# Sediment_Board.net
KiCad netlist of a schematic drawn in EAGLE
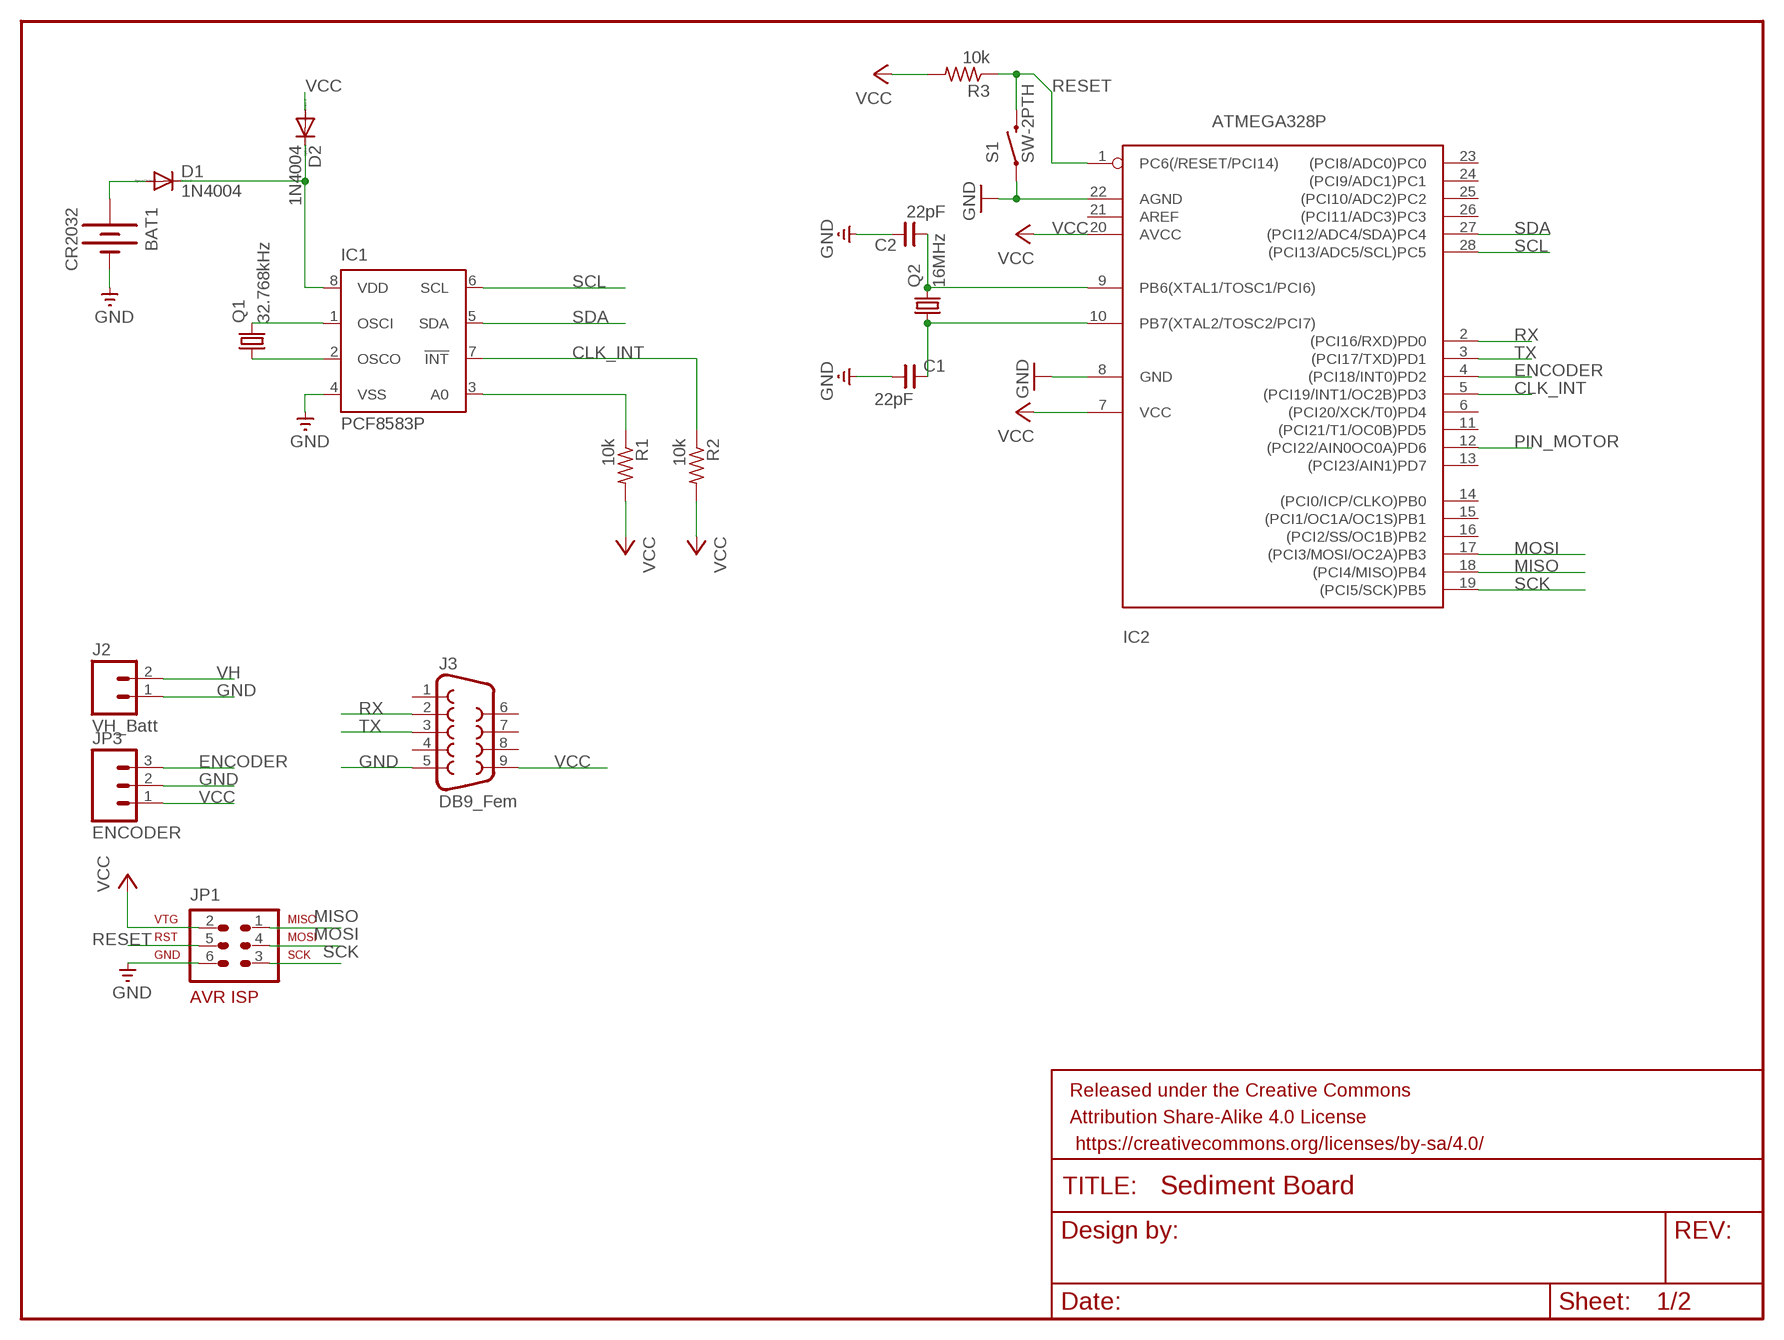
[diagram p0: schematic, sheet 1]
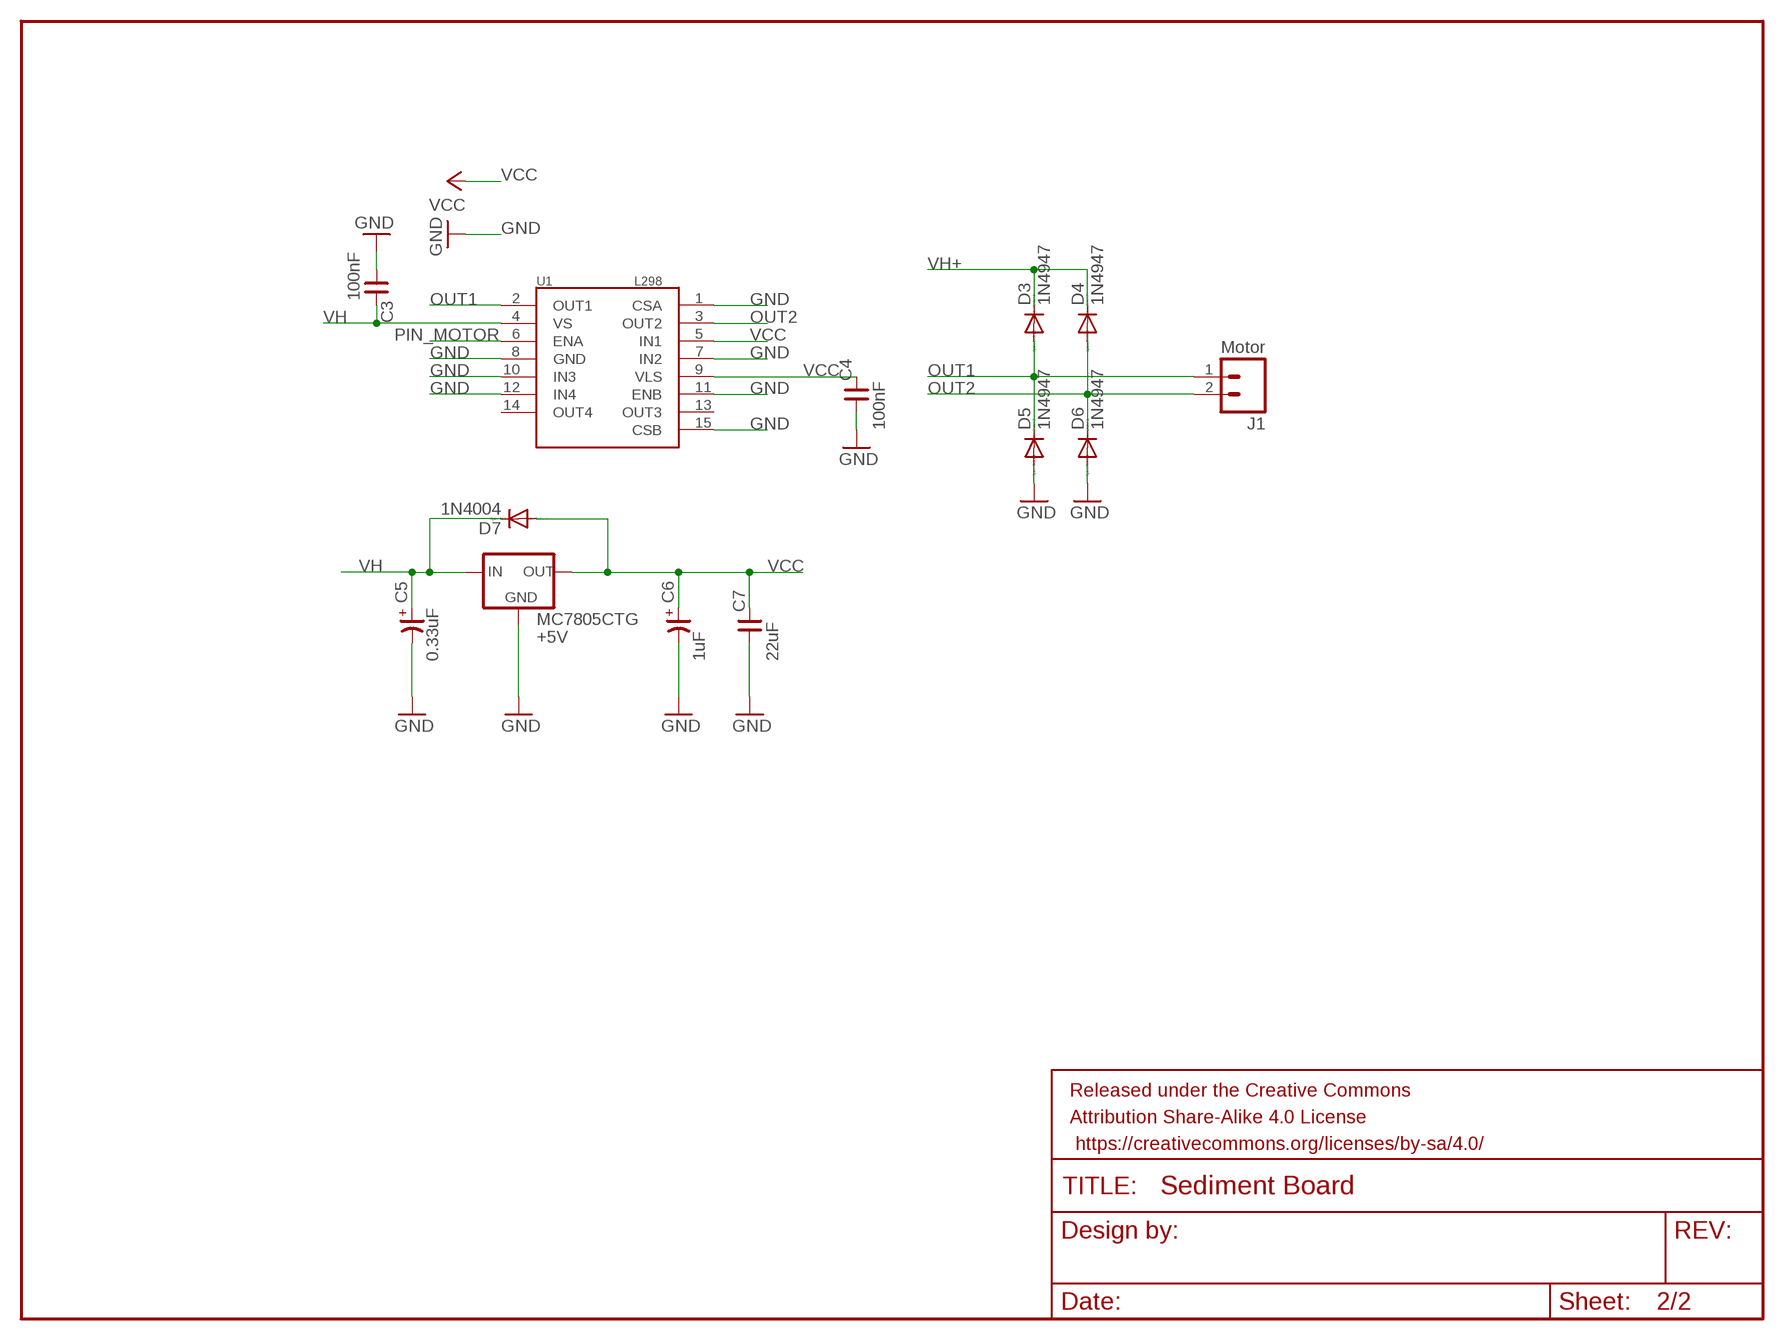
[diagram p1: schematic, sheet 2]

(export (version "E")
  (design (tool "Eeschema 10.0.6"))
  (components
    (comp (ref "C3")
      (value "100nF")
      (footprint "eagle-import:C025-050X025")
      (libsource (lib "eagle-import") (part "CNP-C025-050X025"))
    )
    (comp (ref "C4")
      (value "100nF")
      (footprint "eagle-import:C025-050X025")
      (libsource (lib "eagle-import") (part "CNP-C025-050X025"))
    )
    (comp (ref "C5")
      (value "0.33uF")
      (footprint "eagle-import:TT-025-040")
      (libsource (lib "eagle-import") (part "CP-TT025-040"))
    )
    (comp (ref "C6")
      (value "1uF")
      (footprint "eagle-import:TT-025-040")
      (libsource (lib "eagle-import") (part "CP-TT025-040"))
    )
    (comp (ref "C7")
      (value "22uF")
      (footprint "eagle-import:C025-050X025")
      (libsource (lib "eagle-import") (part "CNP-C025-050X025"))
    )
    (comp (ref "D3")
      (value "1N4947")
      (footprint "eagle-import:DO41-10")
      (libsource (lib "eagle-import") (part "1N4942"))
    )
    (comp (ref "D4")
      (value "1N4947")
      (footprint "eagle-import:DO41-10")
      (libsource (lib "eagle-import") (part "1N4942"))
    )
    (comp (ref "D5")
      (value "1N4947")
      (footprint "eagle-import:DO41-10")
      (libsource (lib "eagle-import") (part "1N4942"))
    )
    (comp (ref "D6")
      (value "1N4947")
      (footprint "eagle-import:DO41-10")
      (libsource (lib "eagle-import") (part "1N4942"))
    )
    (comp (ref "D7")
      (value "1N4004")
      (footprint "eagle-import:DO41-10")
      (libsource (lib "eagle-import") (part "1N4004"))
    )
    (comp (ref "FRAME2")
      (value "FRAME-LETTER")
      (footprint "eagle-import:CREATIVE_COMMONS")
      (libsource (lib "eagle-import") (part "FRAME-LETTER"))
    )
    (comp (ref "J1")
      (value "Motor")
      (footprint "eagle-import:SCREWTERMINAL-3.5MM-2")
      (libsource (lib "eagle-import") (part "M023.5MM"))
    )
    (comp (ref "MC7805CTG")
      (value "+5V")
      (footprint "eagle-import:78XXL")
      (libsource (lib "eagle-import") (part "V_REG_78XXSIDE"))
    )
    (comp (ref "U1")
      (value "L298")
      (footprint "eagle-import:MULTIWATT15")
      (libsource (lib "eagle-import") (part "L298"))
    )
    (comp (ref "BAT1")
      (value "CR2032")
      (footprint "eagle-import:BATTCOM_20MM_PTH")
      (libsource (lib "eagle-import") (part "BATTERY20PTH"))
    )
    (comp (ref "C1")
      (value "22pF")
      (footprint "eagle-import:C025-050X025")
      (libsource (lib "eagle-import") (part "CNP-C025-050X025"))
    )
    (comp (ref "C2")
      (value "22pF")
      (footprint "eagle-import:C025-050X025")
      (libsource (lib "eagle-import") (part "CNP-C025-050X025"))
    )
    (comp (ref "D1")
      (value "1N4004")
      (footprint "eagle-import:DO41-10")
      (libsource (lib "eagle-import") (part "1N4004"))
    )
    (comp (ref "D2")
      (value "1N4004")
      (footprint "eagle-import:DO41-10")
      (libsource (lib "eagle-import") (part "1N4004"))
    )
    (comp (ref "FRAME1")
      (value "FRAME-LETTER")
      (footprint "eagle-import:CREATIVE_COMMONS")
      (libsource (lib "eagle-import") (part "FRAME-LETTER"))
    )
    (comp (ref "IC1")
      (value "PCF8583P")
      (footprint "eagle-import:DIL08")
      (libsource (lib "eagle-import") (part "PCF8583P"))
    )
    (comp (ref "IC2")
      (value "ATMEGA328P")
      (footprint "eagle-import:DIL28-3-ROUND")
      (libsource (lib "eagle-import") (part "ATMEGA328PROUND"))
    )
    (comp (ref "J2")
      (value "VH_Batt")
      (footprint "eagle-import:SCREWTERMINAL-3.5MM-2")
      (libsource (lib "eagle-import") (part "M023.5MM"))
    )
    (comp (ref "J3")
      (value "DB9_Fem")
      (footprint "eagle-import:DB9")
      (libsource (lib "eagle-import") (part "DB9FEMALE"))
    )
    (comp (ref "JP1")
      (value "AVR-ISP-6")
      (footprint "eagle-import:AVR-ISP-6")
      (libsource (lib "eagle-import") (part "AVR-ISP-6"))
    )
    (comp (ref "JP3")
      (value "ENCODER")
      (footprint "eagle-import:MOLEX-1X3")
      (libsource (lib "eagle-import") (part "M03POLAR"))
    )
    (comp (ref "Q1")
      (value "32.768kHz")
      (footprint "eagle-import:TC26H")
      (libsource (lib "eagle-import") (part "CRYSTALTC26H"))
    )
    (comp (ref "Q2")
      (value "16MHz")
      (footprint "eagle-import:HC49U70")
      (libsource (lib "eagle-import") (part "CRYSTALHC49U70"))
    )
    (comp (ref "R1")
      (value "10k")
      (footprint "eagle-import:0207_10")
      (libsource (lib "eagle-import") (part "R-US_0207/10"))
    )
    (comp (ref "R2")
      (value "10k")
      (footprint "eagle-import:0207_10")
      (libsource (lib "eagle-import") (part "R-US_0207/10"))
    )
    (comp (ref "R3")
      (value "10k")
      (footprint "eagle-import:0207_10")
      (libsource (lib "eagle-import") (part "R-US_0207/10"))
    )
    (comp (ref "S1")
      (value "SW-2PTH")
      (footprint "eagle-import:TACTILE-PTH")
      (libsource (lib "eagle-import") (part "SWITCH-MOMENTARY-2PTH"))
    )
  )
  (nets
    (net (code "1") (name "CLK_INT") (class "Default")
      (node (ref "IC1") (pin "7") (pinfunction "~{INT}_7") (pintype "open_collector"))
      (node (ref "IC2") (pin "5") (pinfunction "(PCI19/INT1/OC2B)PD3_5") (pintype "bidirectional"))
      (node (ref "R2") (pin "1") (pinfunction "1_1") (pintype "passive"))
    )
    (net (code "2") (name "ENCODER") (class "Default")
      (node (ref "IC2") (pin "4") (pinfunction "(PCI18/INT0)PD2_4") (pintype "bidirectional"))
      (node (ref "JP3") (pin "3") (pinfunction "3_3") (pintype "passive"))
    )
    (net (code "3") (name "GND") (class "Default")
      (node (ref "BAT1") (pin "2") (pinfunction "-_2") (pintype "power_in"))
      (node (ref "C1") (pin "1") (pinfunction "1_1") (pintype "passive"))
      (node (ref "C2") (pin "2") (pinfunction "2_2") (pintype "passive"))
      (node (ref "C3") (pin "1") (pinfunction "1_1") (pintype "passive"))
      (node (ref "C4") (pin "1") (pinfunction "1_1") (pintype "passive"))
      (node (ref "C5") (pin "-") (pinfunction "-_-") (pintype "passive"))
      (node (ref "C6") (pin "-") (pinfunction "-_-") (pintype "passive"))
      (node (ref "C7") (pin "1") (pinfunction "1_1") (pintype "passive"))
      (node (ref "D5") (pin "A") (pinfunction "A_A") (pintype "passive"))
      (node (ref "D6") (pin "A") (pinfunction "A_A") (pintype "passive"))
      (node (ref "IC1") (pin "4") (pinfunction "VSS_4") (pintype "power_in"))
      (node (ref "IC2") (pin "22") (pinfunction "AGND_22") (pintype "bidirectional"))
      (node (ref "IC2") (pin "8") (pinfunction "GND_8") (pintype "bidirectional"))
      (node (ref "J2") (pin "1") (pinfunction "1_1") (pintype "passive"))
      (node (ref "J3") (pin "5") (pinfunction "5_5") (pintype "passive"))
      (node (ref "JP1") (pin "6") (pinfunction "6_6") (pintype "passive"))
      (node (ref "JP3") (pin "2") (pinfunction "2_2") (pintype "passive"))
      (node (ref "MC7805CTG") (pin "GND") (pinfunction "GND_GND") (pintype "input"))
      (node (ref "S1") (pin "1") (pinfunction "1_1") (pintype "passive"))
      (node (ref "U1") (pin "1") (pinfunction "CSA_1") (pintype "bidirectional"))
      (node (ref "U1") (pin "10") (pinfunction "IN3_10") (pintype "bidirectional"))
      (node (ref "U1") (pin "11") (pinfunction "ENB_11") (pintype "bidirectional"))
      (node (ref "U1") (pin "12") (pinfunction "IN4_12") (pintype "bidirectional"))
      (node (ref "U1") (pin "15") (pinfunction "CSB_15") (pintype "bidirectional"))
      (node (ref "U1") (pin "7") (pinfunction "IN2_7") (pintype "bidirectional"))
      (node (ref "U1") (pin "8") (pinfunction "GND_8") (pintype "bidirectional"))
    )
    (net (code "4") (name "MISO") (class "Default")
      (node (ref "IC2") (pin "18") (pinfunction "(PCI4/MISO)PB4_18") (pintype "bidirectional"))
      (node (ref "JP1") (pin "1") (pinfunction "1_1") (pintype "passive"))
    )
    (net (code "5") (name "MOSI") (class "Default")
      (node (ref "IC2") (pin "17") (pinfunction "(PCI3/MOSI/OC2A)PB3_17") (pintype "bidirectional"))
      (node (ref "JP1") (pin "4") (pinfunction "4_4") (pintype "passive"))
    )
    (net (code "6") (name "Net-(BAT1-+)") (class "Default")
      (node (ref "BAT1") (pin "1") (pinfunction "+_1") (pintype "power_in"))
      (node (ref "D1") (pin "A") (pinfunction "A_A") (pintype "passive"))
    )
    (net (code "7") (name "Net-(IC1-A0)") (class "Default")
      (node (ref "IC1") (pin "3") (pinfunction "A0_3") (pintype "input"))
      (node (ref "R1") (pin "1") (pinfunction "1_1") (pintype "passive"))
    )
    (net (code "8") (name "Net-(IC1-OSCI)") (class "Default")
      (node (ref "IC1") (pin "1") (pinfunction "OSCI_1") (pintype "input"))
      (node (ref "Q1") (pin "2") (pinfunction "2_2") (pintype "passive"))
    )
    (net (code "9") (name "Net-(IC1-OSCO)") (class "Default")
      (node (ref "IC1") (pin "2") (pinfunction "OSCO_2") (pintype "output"))
      (node (ref "Q1") (pin "1") (pinfunction "1_1") (pintype "passive"))
    )
    (net (code "10") (name "Net-(IC1-VDD)") (class "Default")
      (node (ref "D1") (pin "C") (pinfunction "C_C") (pintype "passive"))
      (node (ref "D2") (pin "C") (pinfunction "C_C") (pintype "passive"))
      (node (ref "IC1") (pin "8") (pinfunction "VDD_8") (pintype "power_in"))
    )
    (net (code "11") (name "Net-(IC2-PB6(XTAL1{slash}TOSC1{slash}PCI6))") (class "Default")
      (node (ref "C2") (pin "1") (pinfunction "1_1") (pintype "passive"))
      (node (ref "IC2") (pin "9") (pinfunction "PB6(XTAL1/TOSC1/PCI6)_9") (pintype "bidirectional"))
      (node (ref "Q2") (pin "2") (pinfunction "2_2") (pintype "passive"))
    )
    (net (code "12") (name "Net-(IC2-PB7(XTAL2{slash}TOSC2{slash}PCI7))") (class "Default")
      (node (ref "C1") (pin "2") (pinfunction "2_2") (pintype "passive"))
      (node (ref "IC2") (pin "10") (pinfunction "PB7(XTAL2/TOSC2/PCI7)_10") (pintype "bidirectional"))
      (node (ref "Q2") (pin "1") (pinfunction "1_1") (pintype "passive"))
    )
    (net (code "13") (name "OUT1") (class "Default")
      (node (ref "D3") (pin "A") (pinfunction "A_A") (pintype "passive"))
      (node (ref "D5") (pin "C") (pinfunction "C_C") (pintype "passive"))
      (node (ref "J1") (pin "1") (pinfunction "1_1") (pintype "passive"))
      (node (ref "U1") (pin "2") (pinfunction "OUT1_2") (pintype "bidirectional"))
    )
    (net (code "14") (name "OUT2") (class "Default")
      (node (ref "D4") (pin "A") (pinfunction "A_A") (pintype "passive"))
      (node (ref "D6") (pin "C") (pinfunction "C_C") (pintype "passive"))
      (node (ref "J1") (pin "2") (pinfunction "2_2") (pintype "passive"))
      (node (ref "U1") (pin "3") (pinfunction "OUT2_3") (pintype "bidirectional"))
    )
    (net (code "15") (name "PIN_MOTOR") (class "Default")
      (node (ref "IC2") (pin "12") (pinfunction "(PCI22/AIN0OC0A)PD6_12") (pintype "bidirectional"))
      (node (ref "U1") (pin "6") (pinfunction "ENA_6") (pintype "bidirectional"))
    )
    (net (code "16") (name "RESET") (class "Default")
      (node (ref "IC2") (pin "1") (pinfunction "PC6(/RESET/PCI14)_1") (pintype "bidirectional"))
      (node (ref "JP1") (pin "5") (pinfunction "5_5") (pintype "passive"))
      (node (ref "R3") (pin "1") (pinfunction "1_1") (pintype "passive"))
      (node (ref "S1") (pin "3") (pinfunction "2_3") (pintype "passive"))
    )
    (net (code "17") (name "RX") (class "Default")
      (node (ref "IC2") (pin "2") (pinfunction "(PCI16/RXD)PD0_2") (pintype "bidirectional"))
      (node (ref "J3") (pin "2") (pinfunction "2_2") (pintype "passive"))
    )
    (net (code "18") (name "SCK") (class "Default")
      (node (ref "IC2") (pin "19") (pinfunction "(PCI5/SCK)PB5_19") (pintype "bidirectional"))
      (node (ref "JP1") (pin "3") (pinfunction "3_3") (pintype "passive"))
    )
    (net (code "19") (name "SCL") (class "Default")
      (node (ref "IC1") (pin "6") (pinfunction "SCL_6") (pintype "input"))
      (node (ref "IC2") (pin "28") (pinfunction "(PCI13/ADC5/SCL)PC5_28") (pintype "bidirectional"))
    )
    (net (code "20") (name "SDA") (class "Default")
      (node (ref "IC1") (pin "5") (pinfunction "SDA_5") (pintype "bidirectional"))
      (node (ref "IC2") (pin "27") (pinfunction "(PCI12/ADC4/SDA)PC4_27") (pintype "bidirectional"))
    )
    (net (code "21") (name "TX") (class "Default")
      (node (ref "IC2") (pin "3") (pinfunction "(PCI17/TXD)PD1_3") (pintype "bidirectional"))
      (node (ref "J3") (pin "3") (pinfunction "3_3") (pintype "passive"))
    )
    (net (code "22") (name "VCC") (class "Default")
      (node (ref "C4") (pin "2") (pinfunction "2_2") (pintype "passive"))
      (node (ref "C6") (pin "+") (pinfunction "+_+") (pintype "passive"))
      (node (ref "C7") (pin "2") (pinfunction "2_2") (pintype "passive"))
      (node (ref "D2") (pin "A") (pinfunction "A_A") (pintype "passive"))
      (node (ref "D7") (pin "A") (pinfunction "A_A") (pintype "passive"))
      (node (ref "IC2") (pin "20") (pinfunction "AVCC_20") (pintype "bidirectional"))
      (node (ref "IC2") (pin "7") (pinfunction "VCC_7") (pintype "bidirectional"))
      (node (ref "J3") (pin "9") (pinfunction "9_9") (pintype "passive"))
      (node (ref "JP1") (pin "2") (pinfunction "2_2") (pintype "passive"))
      (node (ref "JP3") (pin "1") (pinfunction "1_1") (pintype "passive"))
      (node (ref "MC7805CTG") (pin "OUT") (pinfunction "OUT_OUT") (pintype "output"))
      (node (ref "R1") (pin "2") (pinfunction "2_2") (pintype "passive"))
      (node (ref "R2") (pin "2") (pinfunction "2_2") (pintype "passive"))
      (node (ref "R3") (pin "2") (pinfunction "2_2") (pintype "passive"))
      (node (ref "U1") (pin "5") (pinfunction "IN1_5") (pintype "bidirectional"))
      (node (ref "U1") (pin "9") (pinfunction "VLS_9") (pintype "bidirectional"))
    )
    (net (code "23") (name "VH") (class "Default")
      (node (ref "C3") (pin "2") (pinfunction "2_2") (pintype "passive"))
      (node (ref "C5") (pin "+") (pinfunction "+_+") (pintype "passive"))
      (node (ref "D7") (pin "C") (pinfunction "C_C") (pintype "passive"))
      (node (ref "J2") (pin "2") (pinfunction "2_2") (pintype "passive"))
      (node (ref "MC7805CTG") (pin "IN") (pinfunction "IN_IN") (pintype "input"))
      (node (ref "U1") (pin "4") (pinfunction "VS_4") (pintype "bidirectional"))
    )
    (net (code "24") (name "VH+") (class "Default")
      (node (ref "D3") (pin "C") (pinfunction "C_C") (pintype "passive"))
      (node (ref "D4") (pin "C") (pinfunction "C_C") (pintype "passive"))
    )
    (net (code "25") (name "unconnected-(IC2-(PCI0{slash}ICP{slash}CLKO)PB0-Pad14)") (class "Default")
      (node (ref "IC2") (pin "14") (pinfunction "(PCI0/ICP/CLKO)PB0_14") (pintype "bidirectional"))
    )
    (net (code "26") (name "unconnected-(IC2-(PCI1{slash}OC1A{slash}OC1S)PB1-Pad15)") (class "Default")
      (node (ref "IC2") (pin "15") (pinfunction "(PCI1/OC1A/OC1S)PB1_15") (pintype "bidirectional"))
    )
    (net (code "27") (name "unconnected-(IC2-(PCI2{slash}SS{slash}OC1B)PB2-Pad16)") (class "Default")
      (node (ref "IC2") (pin "16") (pinfunction "(PCI2/SS/OC1B)PB2_16") (pintype "bidirectional"))
    )
    (net (code "28") (name "unconnected-(IC2-(PCI8{slash}ADC0)PC0-Pad23)") (class "Default")
      (node (ref "IC2") (pin "23") (pinfunction "(PCI8/ADC0)PC0_23") (pintype "bidirectional"))
    )
    (net (code "29") (name "unconnected-(IC2-(PCI9{slash}ADC1)PC1-Pad24)") (class "Default")
      (node (ref "IC2") (pin "24") (pinfunction "(PCI9/ADC1)PC1_24") (pintype "bidirectional"))
    )
    (net (code "30") (name "unconnected-(IC2-(PCI10{slash}ADC2)PC2-Pad25)") (class "Default")
      (node (ref "IC2") (pin "25") (pinfunction "(PCI10/ADC2)PC2_25") (pintype "bidirectional"))
    )
    (net (code "31") (name "unconnected-(IC2-(PCI11{slash}ADC3)PC3-Pad26)") (class "Default")
      (node (ref "IC2") (pin "26") (pinfunction "(PCI11/ADC3)PC3_26") (pintype "bidirectional"))
    )
    (net (code "32") (name "unconnected-(IC2-(PCI20{slash}XCK{slash}T0)PD4-Pad6)") (class "Default")
      (node (ref "IC2") (pin "6") (pinfunction "(PCI20/XCK/T0)PD4_6") (pintype "bidirectional"))
    )
    (net (code "33") (name "unconnected-(IC2-(PCI21{slash}T1{slash}OC0B)PD5-Pad11)") (class "Default")
      (node (ref "IC2") (pin "11") (pinfunction "(PCI21/T1/OC0B)PD5_11") (pintype "bidirectional"))
    )
    (net (code "34") (name "unconnected-(IC2-(PCI23{slash}AIN1)PD7-Pad13)") (class "Default")
      (node (ref "IC2") (pin "13") (pinfunction "(PCI23/AIN1)PD7_13") (pintype "bidirectional"))
    )
    (net (code "35") (name "unconnected-(IC2-AREF-Pad21)") (class "Default")
      (node (ref "IC2") (pin "21") (pinfunction "AREF_21") (pintype "bidirectional"))
    )
    (net (code "36") (name "unconnected-(J3-Pad1)") (class "Default")
      (node (ref "J3") (pin "1") (pinfunction "1_1") (pintype "passive"))
    )
    (net (code "37") (name "unconnected-(J3-Pad4)") (class "Default")
      (node (ref "J3") (pin "4") (pinfunction "4_4") (pintype "passive"))
    )
    (net (code "38") (name "unconnected-(J3-Pad6)") (class "Default")
      (node (ref "J3") (pin "6") (pinfunction "6_6") (pintype "passive"))
    )
    (net (code "39") (name "unconnected-(J3-Pad7)") (class "Default")
      (node (ref "J3") (pin "7") (pinfunction "7_7") (pintype "passive"))
    )
    (net (code "40") (name "unconnected-(J3-Pad8)") (class "Default")
      (node (ref "J3") (pin "8") (pinfunction "8_8") (pintype "passive"))
    )
    (net (code "41") (name "unconnected-(U1-OUT3-Pad13)") (class "Default")
      (node (ref "U1") (pin "13") (pinfunction "OUT3_13") (pintype "bidirectional"))
    )
    (net (code "42") (name "unconnected-(U1-OUT4-Pad14)") (class "Default")
      (node (ref "U1") (pin "14") (pinfunction "OUT4_14") (pintype "bidirectional"))
    )
  )
)
